# panelDoc.net
KiCad netlist of a schematic drawn in EAGLE
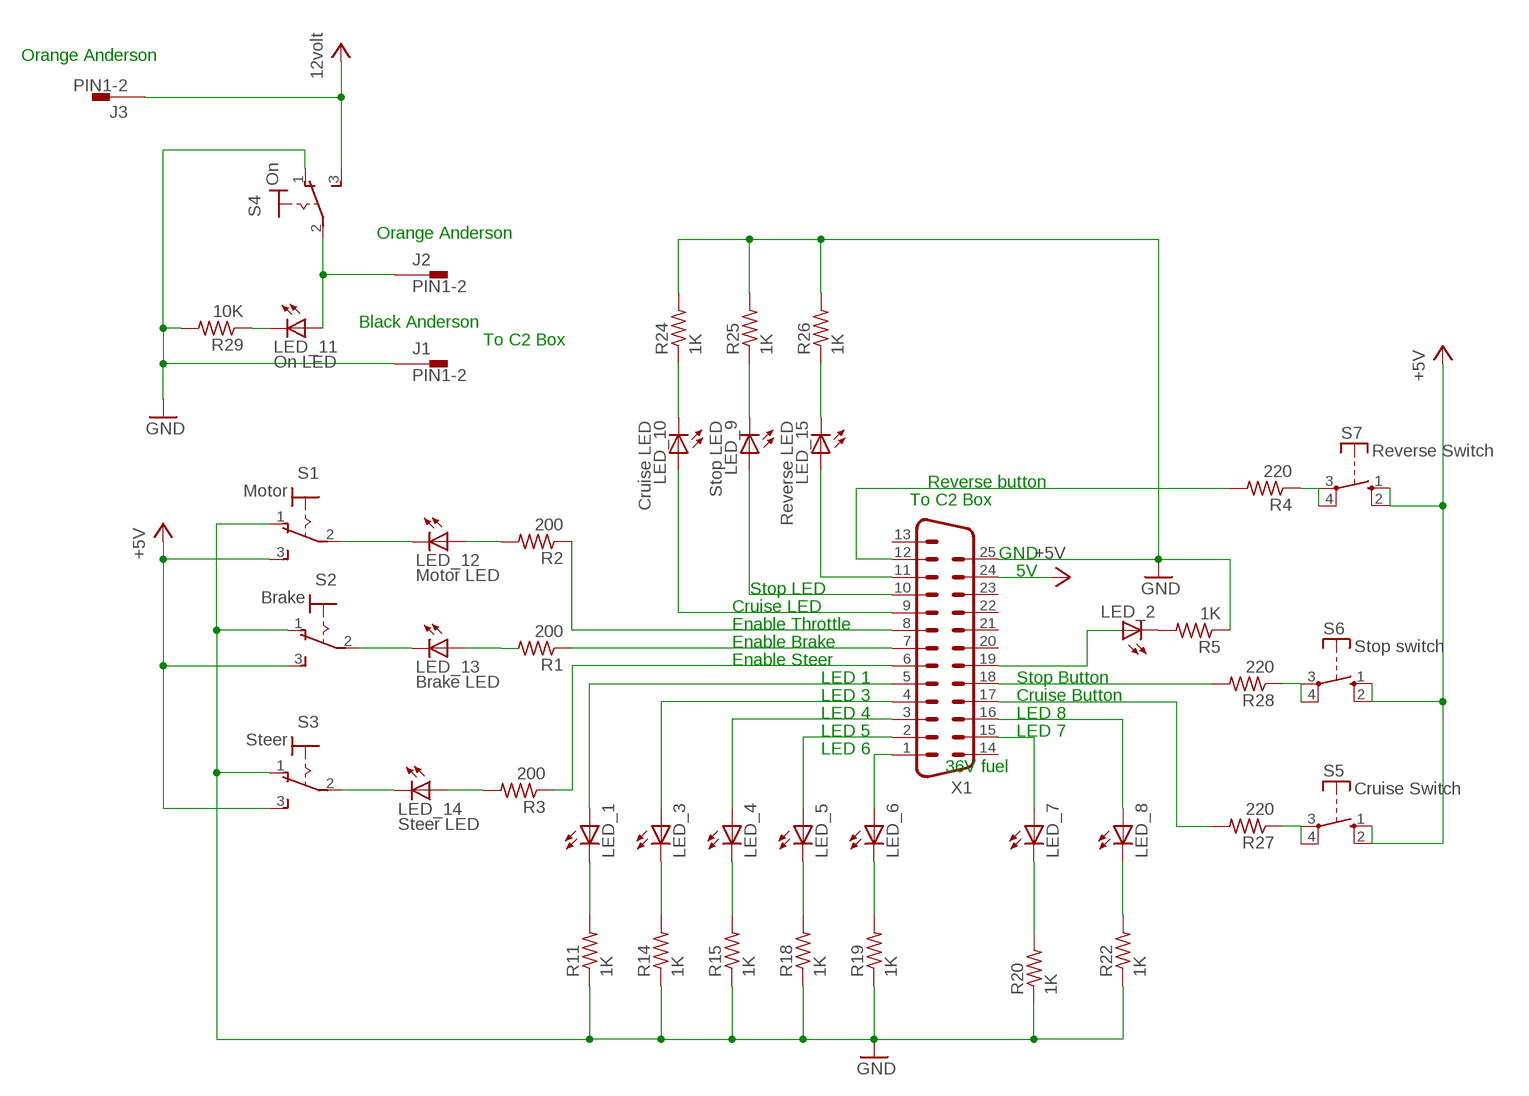
[diagram p0: schematic, sheet 1]

(export (version "E")
  (design (tool "Eeschema 10.0.6"))
  (components
    (comp (ref "J1")
      (value "PIN1-2")
      (footprint "eagle-import:62221")
      (fields (field (name "MF") "TYCO ELECTRONICS") (field (name "MPN") "62221-1"))
      (libsource (lib "eagle-import") (part "PIN1-2"))
    )
    (comp (ref "J2")
      (value "PIN1-2")
      (footprint "eagle-import:62221")
      (fields (field (name "MF") "TYCO ELECTRONICS") (field (name "MPN") "62221-1"))
      (libsource (lib "eagle-import") (part "PIN1-2"))
    )
    (comp (ref "J3")
      (value "PIN1-2")
      (footprint "eagle-import:62221")
      (fields (field (name "MF") "TYCO ELECTRONICS") (field (name "MPN") "62221-1"))
      (libsource (lib "eagle-import") (part "PIN1-2"))
    )
    (comp (ref "LED_1")
      (value "LEDB156")
      (footprint "eagle-import:Q62902-B156")
      (libsource (lib "eagle-import") (part "LEDB156"))
    )
    (comp (ref "LED_2")
      (value "LEDB156")
      (footprint "eagle-import:Q62902-B156")
      (libsource (lib "eagle-import") (part "LEDB156"))
    )
    (comp (ref "LED_3")
      (value "LEDB156")
      (footprint "eagle-import:Q62902-B156")
      (libsource (lib "eagle-import") (part "LEDB156"))
    )
    (comp (ref "LED_4")
      (value "LEDB156")
      (footprint "eagle-import:Q62902-B156")
      (libsource (lib "eagle-import") (part "LEDB156"))
    )
    (comp (ref "LED_5")
      (value "LEDB156")
      (footprint "eagle-import:Q62902-B156")
      (libsource (lib "eagle-import") (part "LEDB156"))
    )
    (comp (ref "LED_6")
      (value "LEDB156")
      (footprint "eagle-import:Q62902-B156")
      (libsource (lib "eagle-import") (part "LEDB156"))
    )
    (comp (ref "LED_7")
      (value "LEDB156")
      (footprint "eagle-import:Q62902-B156")
      (libsource (lib "eagle-import") (part "LEDB156"))
    )
    (comp (ref "LED_8")
      (value "LEDB156")
      (footprint "eagle-import:Q62902-B156")
      (libsource (lib "eagle-import") (part "LEDB156"))
    )
    (comp (ref "LED_9")
      (value "Stop LED")
      (footprint "eagle-import:Q62902-B156")
      (libsource (lib "eagle-import") (part "LEDB156"))
    )
    (comp (ref "LED_10")
      (value "Cruise LED")
      (footprint "eagle-import:Q62902-B156")
      (libsource (lib "eagle-import") (part "LEDB156"))
    )
    (comp (ref "LED_11")
      (value "On LED")
      (footprint "eagle-import:Q62902-B156")
      (libsource (lib "eagle-import") (part "LEDB156"))
    )
    (comp (ref "LED_12")
      (value "Motor LED")
      (footprint "eagle-import:Q62902-B156")
      (libsource (lib "eagle-import") (part "LEDB156"))
    )
    (comp (ref "LED_13")
      (value "Brake LED")
      (footprint "eagle-import:Q62902-B156")
      (libsource (lib "eagle-import") (part "LEDB156"))
    )
    (comp (ref "LED_14")
      (value "Steer LED")
      (footprint "eagle-import:Q62902-B156")
      (libsource (lib "eagle-import") (part "LEDB156"))
    )
    (comp (ref "LED_15")
      (value "Reverse LED")
      (footprint "eagle-import:Q62902-B156")
      (libsource (lib "eagle-import") (part "LEDB156"))
    )
    (comp (ref "R1")
      (value "200")
      (footprint "eagle-import:0204_7")
      (libsource (lib "eagle-import") (part "R-US_0204/7"))
    )
    (comp (ref "R2")
      (value "200")
      (footprint "eagle-import:0204_7")
      (libsource (lib "eagle-import") (part "R-US_0204/7"))
    )
    (comp (ref "R3")
      (value "200")
      (footprint "eagle-import:0204_7")
      (libsource (lib "eagle-import") (part "R-US_0204/7"))
    )
    (comp (ref "R4")
      (value "220")
      (footprint "eagle-import:0204_7")
      (libsource (lib "eagle-import") (part "R-US_0204/7"))
    )
    (comp (ref "R5")
      (value "1K")
      (footprint "eagle-import:0204_7")
      (libsource (lib "eagle-import") (part "R-US_0204/7"))
    )
    (comp (ref "R11")
      (value "1K")
      (footprint "eagle-import:0204_7")
      (libsource (lib "eagle-import") (part "R-US_0204/7"))
    )
    (comp (ref "R14")
      (value "1K")
      (footprint "eagle-import:0204_7")
      (libsource (lib "eagle-import") (part "R-US_0204/7"))
    )
    (comp (ref "R15")
      (value "1K")
      (footprint "eagle-import:0204_7")
      (libsource (lib "eagle-import") (part "R-US_0204/7"))
    )
    (comp (ref "R18")
      (value "1K")
      (footprint "eagle-import:0204_7")
      (libsource (lib "eagle-import") (part "R-US_0204/7"))
    )
    (comp (ref "R19")
      (value "1K")
      (footprint "eagle-import:0204_7")
      (libsource (lib "eagle-import") (part "R-US_0204/7"))
    )
    (comp (ref "R20")
      (value "1K")
      (footprint "eagle-import:0204_7")
      (libsource (lib "eagle-import") (part "R-US_0204/7"))
    )
    (comp (ref "R22")
      (value "1K")
      (footprint "eagle-import:0204_7")
      (libsource (lib "eagle-import") (part "R-US_0204/7"))
    )
    (comp (ref "R24")
      (value "1K")
      (footprint "eagle-import:0204_7")
      (libsource (lib "eagle-import") (part "R-US_0204/7"))
    )
    (comp (ref "R25")
      (value "1K")
      (footprint "eagle-import:0204_7")
      (libsource (lib "eagle-import") (part "R-US_0204/7"))
    )
    (comp (ref "R26")
      (value "1K")
      (footprint "eagle-import:0204_7")
      (libsource (lib "eagle-import") (part "R-US_0204/7"))
    )
    (comp (ref "R27")
      (value "220")
      (footprint "eagle-import:0204_7")
      (libsource (lib "eagle-import") (part "R-US_0204/7"))
    )
    (comp (ref "R28")
      (value "220")
      (footprint "eagle-import:0204_7")
      (libsource (lib "eagle-import") (part "R-US_0204/7"))
    )
    (comp (ref "R29")
      (value "10K")
      (footprint "eagle-import:0204_7")
      (libsource (lib "eagle-import") (part "R-US_0204/7"))
    )
    (comp (ref "S1")
      (value "Motor")
      (footprint "eagle-import:M9040P")
      (libsource (lib "eagle-import") (part "M9040P"))
    )
    (comp (ref "S2")
      (value "Brake")
      (footprint "eagle-import:M9040P")
      (libsource (lib "eagle-import") (part "M9040P"))
    )
    (comp (ref "S3")
      (value "Steer")
      (footprint "eagle-import:M9040P")
      (libsource (lib "eagle-import") (part "M9040P"))
    )
    (comp (ref "S4")
      (value "On")
      (footprint "eagle-import:M9040P")
      (libsource (lib "eagle-import") (part "M9040P"))
    )
    (comp (ref "S5")
      (value "Cruise Switch")
      (footprint "eagle-import:DTE6K")
      (libsource (lib "eagle-import") (part "DTE6K"))
    )
    (comp (ref "S6")
      (value "Stop switch")
      (footprint "eagle-import:DTE6K")
      (libsource (lib "eagle-import") (part "DTE6K"))
    )
    (comp (ref "S7")
      (value "Reverse Switch")
      (footprint "eagle-import:DTE6K")
      (libsource (lib "eagle-import") (part "DTE6K"))
    )
    (comp (ref "X1")
      (value "M25-182")
      (footprint "eagle-import:182-025-MALE")
      (libsource (lib "eagle-import") (part "M25-182"))
    )
  )
  (nets
    (net (code "1") (name "+5V") (class "Default")
      (node (ref "J3") (pin "1") (pinfunction "1_1") (pintype "passive"))
      (node (ref "S1") (pin "3") (pinfunction "S_3") (pintype "passive"))
      (node (ref "S2") (pin "3") (pinfunction "S_3") (pintype "passive"))
      (node (ref "S3") (pin "3") (pinfunction "S_3") (pintype "passive"))
      (node (ref "S4") (pin "3") (pinfunction "S_3") (pintype "passive"))
      (node (ref "S5") (pin "1") (pinfunction "S_1") (pintype "passive"))
      (node (ref "S5") (pin "2") (pinfunction "S_2") (pintype "passive"))
      (node (ref "S6") (pin "1") (pinfunction "S_1") (pintype "passive"))
      (node (ref "S6") (pin "2") (pinfunction "S_2") (pintype "passive"))
      (node (ref "S7") (pin "1") (pinfunction "S_1") (pintype "passive"))
      (node (ref "S7") (pin "2") (pinfunction "S_2") (pintype "passive"))
      (node (ref "X1") (pin "24") (pinfunction "24_24") (pintype "passive"))
    )
    (net (code "2") (name "GND") (class "Default")
      (node (ref "J1") (pin "1") (pinfunction "1_1") (pintype "passive"))
      (node (ref "R11") (pin "1") (pinfunction "1_1") (pintype "passive"))
      (node (ref "R14") (pin "1") (pinfunction "1_1") (pintype "passive"))
      (node (ref "R15") (pin "1") (pinfunction "1_1") (pintype "passive"))
      (node (ref "R18") (pin "1") (pinfunction "1_1") (pintype "passive"))
      (node (ref "R19") (pin "1") (pinfunction "1_1") (pintype "passive"))
      (node (ref "R20") (pin "1") (pinfunction "1_1") (pintype "passive"))
      (node (ref "R22") (pin "1") (pinfunction "1_1") (pintype "passive"))
      (node (ref "R24") (pin "2") (pinfunction "2_2") (pintype "passive"))
      (node (ref "R25") (pin "2") (pinfunction "2_2") (pintype "passive"))
      (node (ref "R26") (pin "2") (pinfunction "2_2") (pintype "passive"))
      (node (ref "R29") (pin "2") (pinfunction "2_2") (pintype "passive"))
      (node (ref "R5") (pin "1") (pinfunction "1_1") (pintype "passive"))
      (node (ref "S1") (pin "1") (pinfunction "O_1") (pintype "passive"))
      (node (ref "S2") (pin "1") (pinfunction "O_1") (pintype "passive"))
      (node (ref "S3") (pin "1") (pinfunction "O_1") (pintype "passive"))
      (node (ref "S4") (pin "1") (pinfunction "O_1") (pintype "passive"))
      (node (ref "X1") (pin "25") (pinfunction "25_25") (pintype "passive"))
    )
    (net (code "3") (name "Net-(LED_1-C)") (class "Default")
      (node (ref "LED_1") (pin "K") (pinfunction "C_K") (pintype "passive"))
      (node (ref "R11") (pin "2") (pinfunction "2_2") (pintype "passive"))
    )
    (net (code "4") (name "Net-(LED_1-PadA)") (class "Default")
      (node (ref "LED_1") (pin "A") (pinfunction "A_A") (pintype "passive"))
      (node (ref "X1") (pin "5") (pinfunction "5_5") (pintype "passive"))
    )
    (net (code "5") (name "Net-(LED_2-C)") (class "Default")
      (node (ref "LED_2") (pin "K") (pinfunction "C_K") (pintype "passive"))
      (node (ref "R5") (pin "2") (pinfunction "2_2") (pintype "passive"))
    )
    (net (code "6") (name "Net-(LED_3-C)") (class "Default")
      (node (ref "LED_3") (pin "K") (pinfunction "C_K") (pintype "passive"))
      (node (ref "R14") (pin "2") (pinfunction "2_2") (pintype "passive"))
    )
    (net (code "7") (name "Net-(LED_3-PadA)") (class "Default")
      (node (ref "LED_3") (pin "A") (pinfunction "A_A") (pintype "passive"))
      (node (ref "X1") (pin "4") (pinfunction "4_4") (pintype "passive"))
    )
    (net (code "8") (name "Net-(LED_4-C)") (class "Default")
      (node (ref "LED_4") (pin "K") (pinfunction "C_K") (pintype "passive"))
      (node (ref "R15") (pin "2") (pinfunction "2_2") (pintype "passive"))
    )
    (net (code "9") (name "Net-(LED_4-PadA)") (class "Default")
      (node (ref "LED_4") (pin "A") (pinfunction "A_A") (pintype "passive"))
      (node (ref "X1") (pin "3") (pinfunction "3_3") (pintype "passive"))
    )
    (net (code "10") (name "Net-(LED_5-C)") (class "Default")
      (node (ref "LED_5") (pin "K") (pinfunction "C_K") (pintype "passive"))
      (node (ref "R18") (pin "2") (pinfunction "2_2") (pintype "passive"))
    )
    (net (code "11") (name "Net-(LED_5-PadA)") (class "Default")
      (node (ref "LED_5") (pin "A") (pinfunction "A_A") (pintype "passive"))
      (node (ref "X1") (pin "2") (pinfunction "2_2") (pintype "passive"))
    )
    (net (code "12") (name "Net-(LED_6-C)") (class "Default")
      (node (ref "LED_6") (pin "K") (pinfunction "C_K") (pintype "passive"))
      (node (ref "R19") (pin "2") (pinfunction "2_2") (pintype "passive"))
    )
    (net (code "13") (name "Net-(LED_6-PadA)") (class "Default")
      (node (ref "LED_6") (pin "A") (pinfunction "A_A") (pintype "passive"))
      (node (ref "X1") (pin "1") (pinfunction "1_1") (pintype "passive"))
    )
    (net (code "14") (name "Net-(LED_7-C)") (class "Default")
      (node (ref "LED_7") (pin "K") (pinfunction "C_K") (pintype "passive"))
      (node (ref "R20") (pin "2") (pinfunction "2_2") (pintype "passive"))
    )
    (net (code "15") (name "Net-(LED_7-PadA)") (class "Default")
      (node (ref "LED_7") (pin "A") (pinfunction "A_A") (pintype "passive"))
      (node (ref "X1") (pin "15") (pinfunction "15_15") (pintype "passive"))
    )
    (net (code "16") (name "Net-(LED_8-C)") (class "Default")
      (node (ref "LED_8") (pin "K") (pinfunction "C_K") (pintype "passive"))
      (node (ref "R22") (pin "2") (pinfunction "2_2") (pintype "passive"))
    )
    (net (code "17") (name "Net-(LED_8-PadA)") (class "Default")
      (node (ref "LED_8") (pin "A") (pinfunction "A_A") (pintype "passive"))
      (node (ref "X1") (pin "16") (pinfunction "16_16") (pintype "passive"))
    )
    (net (code "18") (name "Net-(LED_9-C)") (class "Default")
      (node (ref "LED_9") (pin "K") (pinfunction "C_K") (pintype "passive"))
      (node (ref "R25") (pin "1") (pinfunction "1_1") (pintype "passive"))
    )
    (net (code "19") (name "Net-(LED_9-PadA)") (class "Default")
      (node (ref "LED_9") (pin "A") (pinfunction "A_A") (pintype "passive"))
      (node (ref "X1") (pin "10") (pinfunction "10_10") (pintype "passive"))
    )
    (net (code "20") (name "Net-(LED_10-C)") (class "Default")
      (node (ref "LED_10") (pin "K") (pinfunction "C_K") (pintype "passive"))
      (node (ref "R24") (pin "1") (pinfunction "1_1") (pintype "passive"))
    )
    (net (code "21") (name "Net-(LED_10-PadA)") (class "Default")
      (node (ref "LED_10") (pin "A") (pinfunction "A_A") (pintype "passive"))
      (node (ref "X1") (pin "9") (pinfunction "9_9") (pintype "passive"))
    )
    (net (code "22") (name "Net-(LED_11-C)") (class "Default")
      (node (ref "LED_11") (pin "K") (pinfunction "C_K") (pintype "passive"))
      (node (ref "R29") (pin "1") (pinfunction "1_1") (pintype "passive"))
    )
    (net (code "23") (name "Net-(LED_12-C)") (class "Default")
      (node (ref "LED_12") (pin "K") (pinfunction "C_K") (pintype "passive"))
      (node (ref "S1") (pin "2") (pinfunction "P_2") (pintype "passive"))
    )
    (net (code "24") (name "Net-(LED_12-PadA)") (class "Default")
      (node (ref "LED_12") (pin "A") (pinfunction "A_A") (pintype "passive"))
      (node (ref "R2") (pin "2") (pinfunction "2_2") (pintype "passive"))
    )
    (net (code "25") (name "Net-(LED_13-C)") (class "Default")
      (node (ref "LED_13") (pin "K") (pinfunction "C_K") (pintype "passive"))
      (node (ref "S2") (pin "2") (pinfunction "P_2") (pintype "passive"))
    )
    (net (code "26") (name "Net-(LED_13-PadA)") (class "Default")
      (node (ref "LED_13") (pin "A") (pinfunction "A_A") (pintype "passive"))
      (node (ref "R1") (pin "2") (pinfunction "2_2") (pintype "passive"))
    )
    (net (code "27") (name "Net-(LED_14-C)") (class "Default")
      (node (ref "LED_14") (pin "K") (pinfunction "C_K") (pintype "passive"))
      (node (ref "S3") (pin "2") (pinfunction "P_2") (pintype "passive"))
    )
    (net (code "28") (name "Net-(LED_14-PadA)") (class "Default")
      (node (ref "LED_14") (pin "A") (pinfunction "A_A") (pintype "passive"))
      (node (ref "R3") (pin "2") (pinfunction "2_2") (pintype "passive"))
    )
    (net (code "29") (name "Net-(LED_15-C)") (class "Default")
      (node (ref "LED_15") (pin "K") (pinfunction "C_K") (pintype "passive"))
      (node (ref "R26") (pin "1") (pinfunction "1_1") (pintype "passive"))
    )
    (net (code "30") (name "Net-(LED_15-PadA)") (class "Default")
      (node (ref "LED_15") (pin "A") (pinfunction "A_A") (pintype "passive"))
      (node (ref "X1") (pin "11") (pinfunction "11_11") (pintype "passive"))
    )
    (net (code "31") (name "Net-(R1-Pad1)") (class "Default")
      (node (ref "R1") (pin "1") (pinfunction "1_1") (pintype "passive"))
      (node (ref "X1") (pin "7") (pinfunction "7_7") (pintype "passive"))
    )
    (net (code "32") (name "Net-(R2-Pad1)") (class "Default")
      (node (ref "R2") (pin "1") (pinfunction "1_1") (pintype "passive"))
      (node (ref "X1") (pin "8") (pinfunction "8_8") (pintype "passive"))
    )
    (net (code "33") (name "Net-(R3-Pad1)") (class "Default")
      (node (ref "R3") (pin "1") (pinfunction "1_1") (pintype "passive"))
      (node (ref "X1") (pin "6") (pinfunction "6_6") (pintype "passive"))
    )
    (net (code "34") (name "Net-(R4-Pad1)") (class "Default")
      (node (ref "R4") (pin "1") (pinfunction "1_1") (pintype "passive"))
      (node (ref "S7") (pin "3") (pinfunction "P_3") (pintype "passive"))
      (node (ref "S7") (pin "4") (pinfunction "P_4") (pintype "passive"))
    )
    (net (code "35") (name "Net-(R4-Pad2)") (class "Default")
      (node (ref "R4") (pin "2") (pinfunction "2_2") (pintype "passive"))
      (node (ref "X1") (pin "12") (pinfunction "12_12") (pintype "passive"))
    )
    (net (code "36") (name "Net-(R27-Pad1)") (class "Default")
      (node (ref "R27") (pin "1") (pinfunction "1_1") (pintype "passive"))
      (node (ref "S5") (pin "3") (pinfunction "P_3") (pintype "passive"))
      (node (ref "S5") (pin "4") (pinfunction "P_4") (pintype "passive"))
    )
    (net (code "37") (name "Net-(R27-Pad2)") (class "Default")
      (node (ref "R27") (pin "2") (pinfunction "2_2") (pintype "passive"))
      (node (ref "X1") (pin "17") (pinfunction "17_17") (pintype "passive"))
    )
    (net (code "38") (name "Net-(R28-Pad1)") (class "Default")
      (node (ref "R28") (pin "1") (pinfunction "1_1") (pintype "passive"))
      (node (ref "S6") (pin "3") (pinfunction "P_3") (pintype "passive"))
      (node (ref "S6") (pin "4") (pinfunction "P_4") (pintype "passive"))
    )
    (net (code "39") (name "Net-(R28-Pad2)") (class "Default")
      (node (ref "R28") (pin "2") (pinfunction "2_2") (pintype "passive"))
      (node (ref "X1") (pin "18") (pinfunction "18_18") (pintype "passive"))
    )
    (net (code "40") (name "Net-(S4-P)") (class "Default")
      (node (ref "J2") (pin "1") (pinfunction "1_1") (pintype "passive"))
      (node (ref "LED_11") (pin "A") (pinfunction "A_A") (pintype "passive"))
      (node (ref "S4") (pin "2") (pinfunction "P_2") (pintype "passive"))
    )
    (net (code "41") (name "unconnected-(LED_2-PadA)") (class "Default")
      (node (ref "LED_2") (pin "A") (pinfunction "A_A") (pintype "passive"))
    )
    (net (code "42") (name "unconnected-(X1-Pad13)") (class "Default")
      (node (ref "X1") (pin "13") (pinfunction "13_13") (pintype "passive"))
    )
    (net (code "43") (name "unconnected-(X1-Pad14)") (class "Default")
      (node (ref "X1") (pin "14") (pinfunction "14_14") (pintype "passive"))
    )
    (net (code "44") (name "unconnected-(X1-Pad19)") (class "Default")
      (node (ref "X1") (pin "19") (pinfunction "19_19") (pintype "passive"))
    )
    (net (code "45") (name "unconnected-(X1-Pad20)") (class "Default")
      (node (ref "X1") (pin "20") (pinfunction "20_20") (pintype "passive"))
    )
    (net (code "46") (name "unconnected-(X1-Pad21)") (class "Default")
      (node (ref "X1") (pin "21") (pinfunction "21_21") (pintype "passive"))
    )
    (net (code "47") (name "unconnected-(X1-Pad22)") (class "Default")
      (node (ref "X1") (pin "22") (pinfunction "22_22") (pintype "passive"))
    )
    (net (code "48") (name "unconnected-(X1-Pad23)") (class "Default")
      (node (ref "X1") (pin "23") (pinfunction "23_23") (pintype "passive"))
    )
  )
)
